# alimentation-1.net
KiCad netlist of a schematic drawn in EAGLE
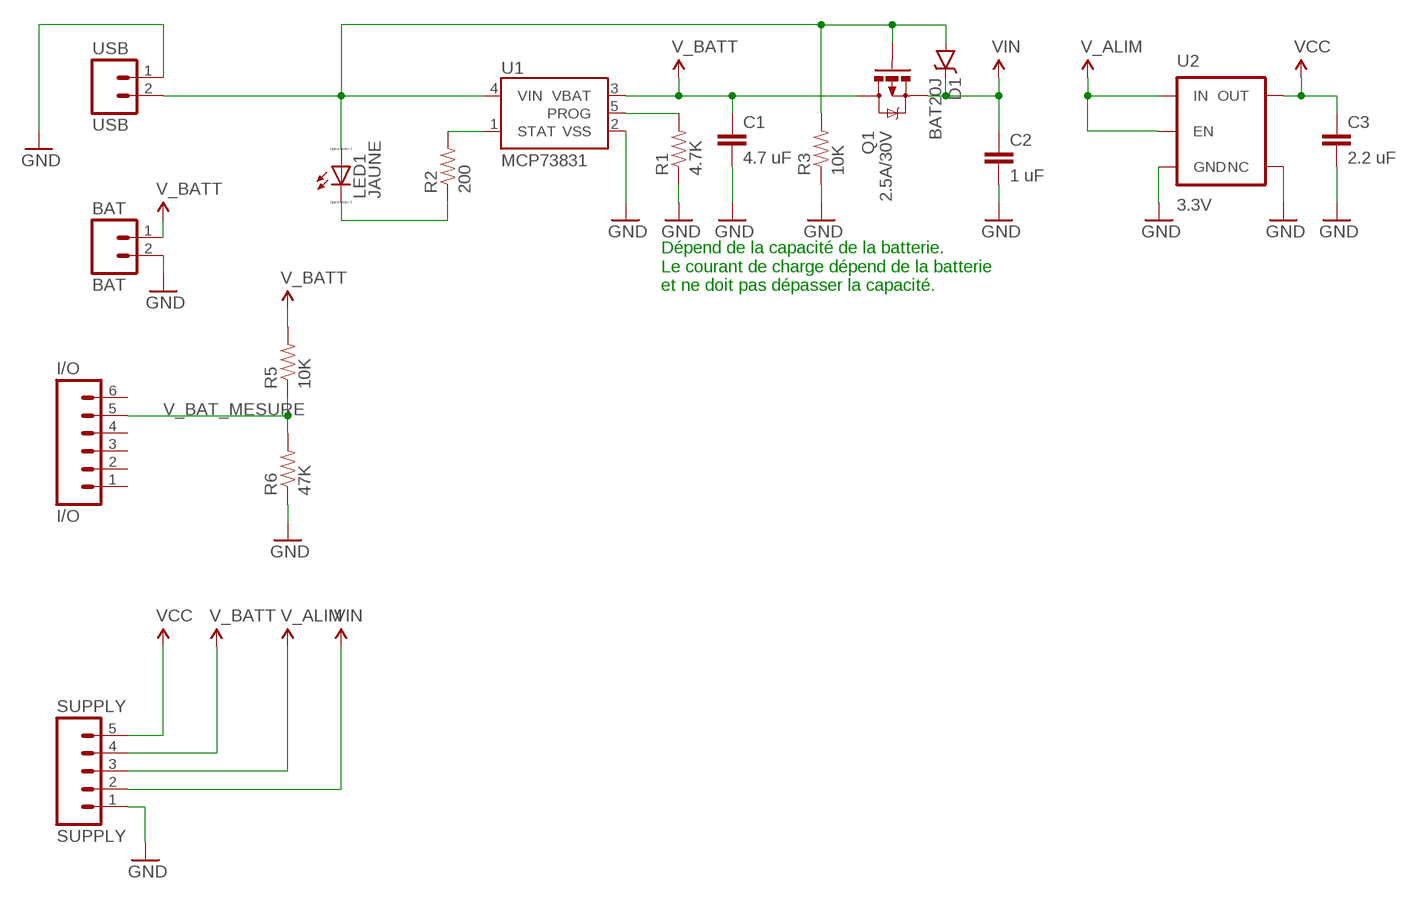
[diagram p0: schematic, sheet 1]

(export (version "E")
  (design (tool "Eeschema 10.0.6"))
  (components
    (comp (ref "BAT")
      (value "BAT")
      (footprint "eagle-import:1X02_NO_SILK")
      (libsource (lib "eagle-import") (part "M021X02_NO_SILK"))
    )
    (comp (ref "C1")
      (value "4.7 uF")
      (footprint "eagle-import:0805")
      (libsource (lib "eagle-import") (part "CAP0805"))
    )
    (comp (ref "C2")
      (value "1 uF")
      (footprint "eagle-import:0805")
      (libsource (lib "eagle-import") (part "CAP0805"))
    )
    (comp (ref "C3")
      (value "2.2 uF")
      (footprint "eagle-import:0805")
      (libsource (lib "eagle-import") (part "CAP0805"))
    )
    (comp (ref "D1")
      (value "BAT20J")
      (footprint "eagle-import:SOD-323")
      (libsource (lib "eagle-import") (part "DIODE-SCHOTTKY-BAT20J"))
    )
    (comp (ref "I/O")
      (value "I/O")
      (footprint "eagle-import:1X06_NO_SILK")
      (libsource (lib "eagle-import") (part "M06NO_SILK_FEMALE_PTH"))
    )
    (comp (ref "LED1")
      (value "JAUNE")
      (footprint "eagle-import:LED_1206")
      (libsource (lib "eagle-import") (part "LED_E"))
    )
    (comp (ref "Q1")
      (value "2.5A/30V")
      (footprint "eagle-import:SOT23-3")
      (libsource (lib "eagle-import") (part "MOSFET-PCHANNELDMG2307L"))
    )
    (comp (ref "R1")
      (value "4.7K")
      (footprint "eagle-import:0805")
      (libsource (lib "eagle-import") (part "RESISTOR0805-RES"))
    )
    (comp (ref "R2")
      (value "200")
      (footprint "eagle-import:0805")
      (libsource (lib "eagle-import") (part "RESISTOR0805-RES"))
    )
    (comp (ref "R3")
      (value "10K")
      (footprint "eagle-import:0805")
      (libsource (lib "eagle-import") (part "RESISTOR0805-RES"))
    )
    (comp (ref "R5")
      (value "10K")
      (footprint "eagle-import:0805")
      (libsource (lib "eagle-import") (part "RESISTOR0805-RES"))
    )
    (comp (ref "R6")
      (value "47K")
      (footprint "eagle-import:0805")
      (libsource (lib "eagle-import") (part "RESISTOR0805-RES"))
    )
    (comp (ref "SUPPLY")
      (value "SUPPLY")
      (footprint "eagle-import:1X05_NO_SILK")
      (libsource (lib "eagle-import") (part "M05NO_SILK"))
    )
    (comp (ref "U1")
      (value "MCP73831")
      (footprint "eagle-import:SOT23-5")
      (libsource (lib "eagle-import") (part "MCP73831"))
    )
    (comp (ref "U2")
      (value "3.3V")
      (footprint "eagle-import:SOT23-5")
      (libsource (lib "eagle-import") (part "V_REG_AP2112K-3.3V"))
    )
    (comp (ref "USB")
      (value "USB")
      (footprint "eagle-import:1X02_NO_SILK")
      (libsource (lib "eagle-import") (part "M021X02_NO_SILK"))
    )
  )
  (nets
    (net (code "1") (name "/V_BAT_MESURE") (class "Default")
      (node (ref "I/O") (pin "5") (pinfunction "5_5") (pintype "passive"))
      (node (ref "R5") (pin "1") (pinfunction "1_1") (pintype "passive"))
      (node (ref "R6") (pin "2") (pinfunction "2_2") (pintype "passive"))
    )
    (net (code "2") (name "GND") (class "Default")
      (node (ref "BAT") (pin "2") (pinfunction "2_2") (pintype "passive"))
      (node (ref "C1") (pin "2") (pinfunction "2_2") (pintype "passive"))
      (node (ref "C2") (pin "2") (pinfunction "2_2") (pintype "passive"))
      (node (ref "C3") (pin "2") (pinfunction "2_2") (pintype "passive"))
      (node (ref "R1") (pin "1") (pinfunction "1_1") (pintype "passive"))
      (node (ref "R3") (pin "1") (pinfunction "1_1") (pintype "passive"))
      (node (ref "R6") (pin "1") (pinfunction "1_1") (pintype "passive"))
      (node (ref "SUPPLY") (pin "1") (pinfunction "1_1") (pintype "passive"))
      (node (ref "U1") (pin "2") (pinfunction "VSS_2") (pintype "power_in"))
      (node (ref "U2") (pin "2") (pinfunction "GND_2") (pintype "input"))
      (node (ref "U2") (pin "4") (pinfunction "NC_4") (pintype "input"))
      (node (ref "USB") (pin "1") (pinfunction "1_1") (pintype "passive"))
    )
    (net (code "3") (name "Net-(LED1-PadC)") (class "Default")
      (node (ref "LED1") (pin "C") (pinfunction "C_C") (pintype "passive"))
      (node (ref "R2") (pin "1") (pinfunction "1_1") (pintype "passive"))
    )
    (net (code "4") (name "Net-(Q1-G)") (class "Default")
      (node (ref "D1") (pin "A") (pinfunction "A_A") (pintype "passive"))
      (node (ref "LED1") (pin "A") (pinfunction "A_A") (pintype "passive"))
      (node (ref "Q1") (pin "1") (pinfunction "G_1") (pintype "passive"))
      (node (ref "R3") (pin "2") (pinfunction "2_2") (pintype "passive"))
      (node (ref "U1") (pin "4") (pinfunction "VIN_4") (pintype "power_in"))
      (node (ref "USB") (pin "2") (pinfunction "2_2") (pintype "passive"))
    )
    (net (code "5") (name "Net-(U1-PROG)") (class "Default")
      (node (ref "R1") (pin "2") (pinfunction "2_2") (pintype "passive"))
      (node (ref "U1") (pin "5") (pinfunction "PROG_5") (pintype "input"))
    )
    (net (code "6") (name "Net-(U1-STAT)") (class "Default")
      (node (ref "R2") (pin "2") (pinfunction "2_2") (pintype "passive"))
      (node (ref "U1") (pin "1") (pinfunction "STAT_1") (pintype "output"))
    )
    (net (code "7") (name "VCC") (class "Default")
      (node (ref "C3") (pin "1") (pinfunction "1_1") (pintype "passive"))
      (node (ref "SUPPLY") (pin "5") (pinfunction "5_5") (pintype "passive"))
      (node (ref "U2") (pin "5") (pinfunction "OUT_5") (pintype "passive"))
    )
    (net (code "8") (name "VIN") (class "Default")
      (node (ref "C2") (pin "1") (pinfunction "1_1") (pintype "passive"))
      (node (ref "D1") (pin "C") (pinfunction "C_C") (pintype "passive"))
      (node (ref "Q1") (pin "2") (pinfunction "S_2") (pintype "passive"))
      (node (ref "SUPPLY") (pin "2") (pinfunction "2_2") (pintype "passive"))
    )
    (net (code "9") (name "V_ALIM") (class "Default")
      (node (ref "SUPPLY") (pin "3") (pinfunction "3_3") (pintype "passive"))
      (node (ref "U2") (pin "1") (pinfunction "IN_1") (pintype "input"))
      (node (ref "U2") (pin "3") (pinfunction "EN_3") (pintype "input"))
    )
    (net (code "10") (name "V_BATT") (class "Default")
      (node (ref "BAT") (pin "1") (pinfunction "1_1") (pintype "passive"))
      (node (ref "C1") (pin "1") (pinfunction "1_1") (pintype "passive"))
      (node (ref "Q1") (pin "3") (pinfunction "D_3") (pintype "passive"))
      (node (ref "R5") (pin "2") (pinfunction "2_2") (pintype "passive"))
      (node (ref "SUPPLY") (pin "4") (pinfunction "4_4") (pintype "passive"))
      (node (ref "U1") (pin "3") (pinfunction "VBAT_3") (pintype "power_in"))
    )
    (net (code "11") (name "unconnected-(I/O-Pad1)") (class "Default")
      (node (ref "I/O") (pin "1") (pinfunction "1_1") (pintype "passive"))
    )
    (net (code "12") (name "unconnected-(I/O-Pad2)") (class "Default")
      (node (ref "I/O") (pin "2") (pinfunction "2_2") (pintype "passive"))
    )
    (net (code "13") (name "unconnected-(I/O-Pad3)") (class "Default")
      (node (ref "I/O") (pin "3") (pinfunction "3_3") (pintype "passive"))
    )
    (net (code "14") (name "unconnected-(I/O-Pad4)") (class "Default")
      (node (ref "I/O") (pin "4") (pinfunction "4_4") (pintype "passive"))
    )
    (net (code "15") (name "unconnected-(I/O-Pad6)") (class "Default")
      (node (ref "I/O") (pin "6") (pinfunction "6_6") (pintype "passive"))
    )
  )
)
